# Carrier_Board_PIR.net
KiCad netlist of a schematic drawn in EAGLE
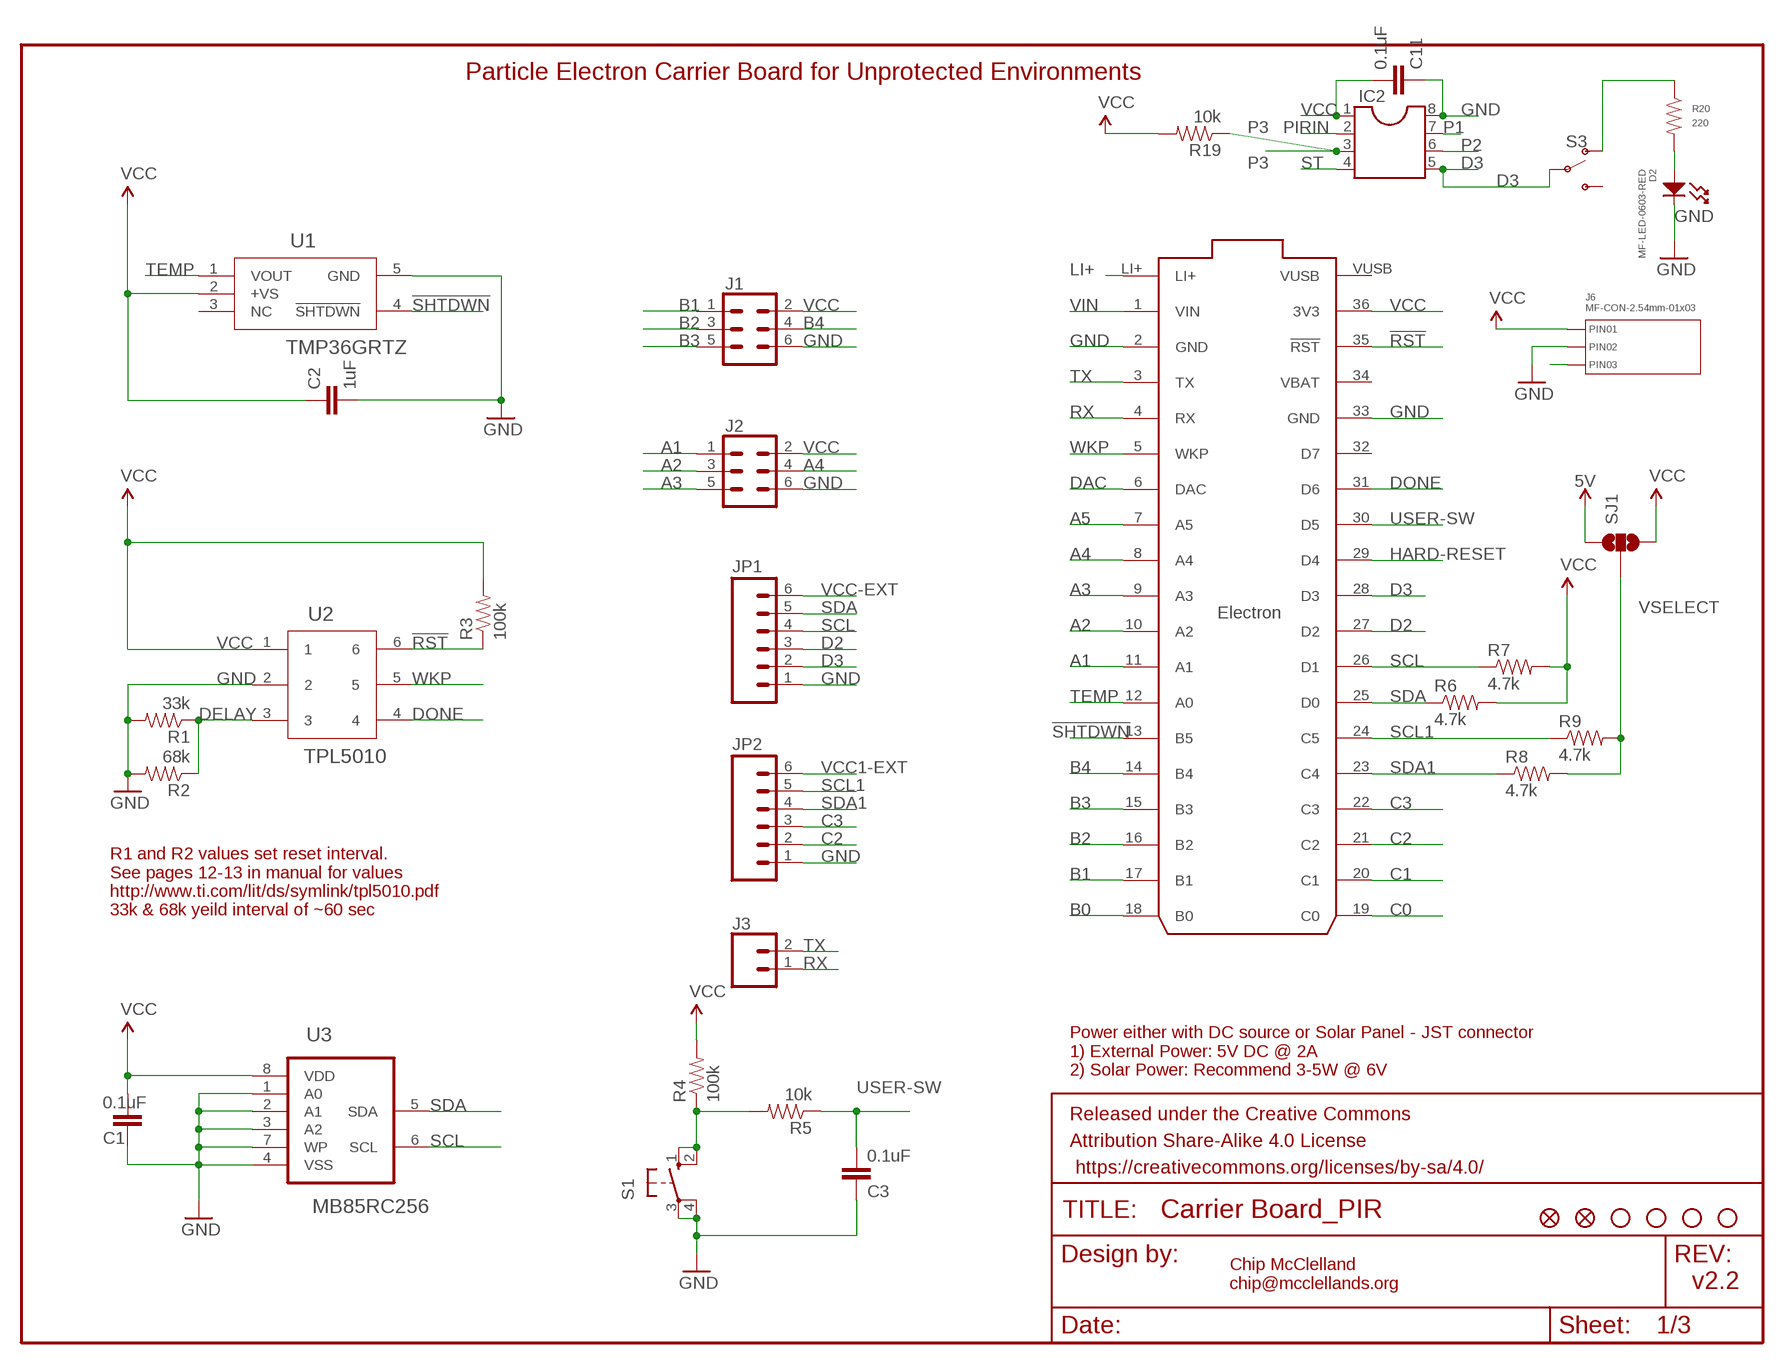
[diagram p0: schematic, sheet 1]
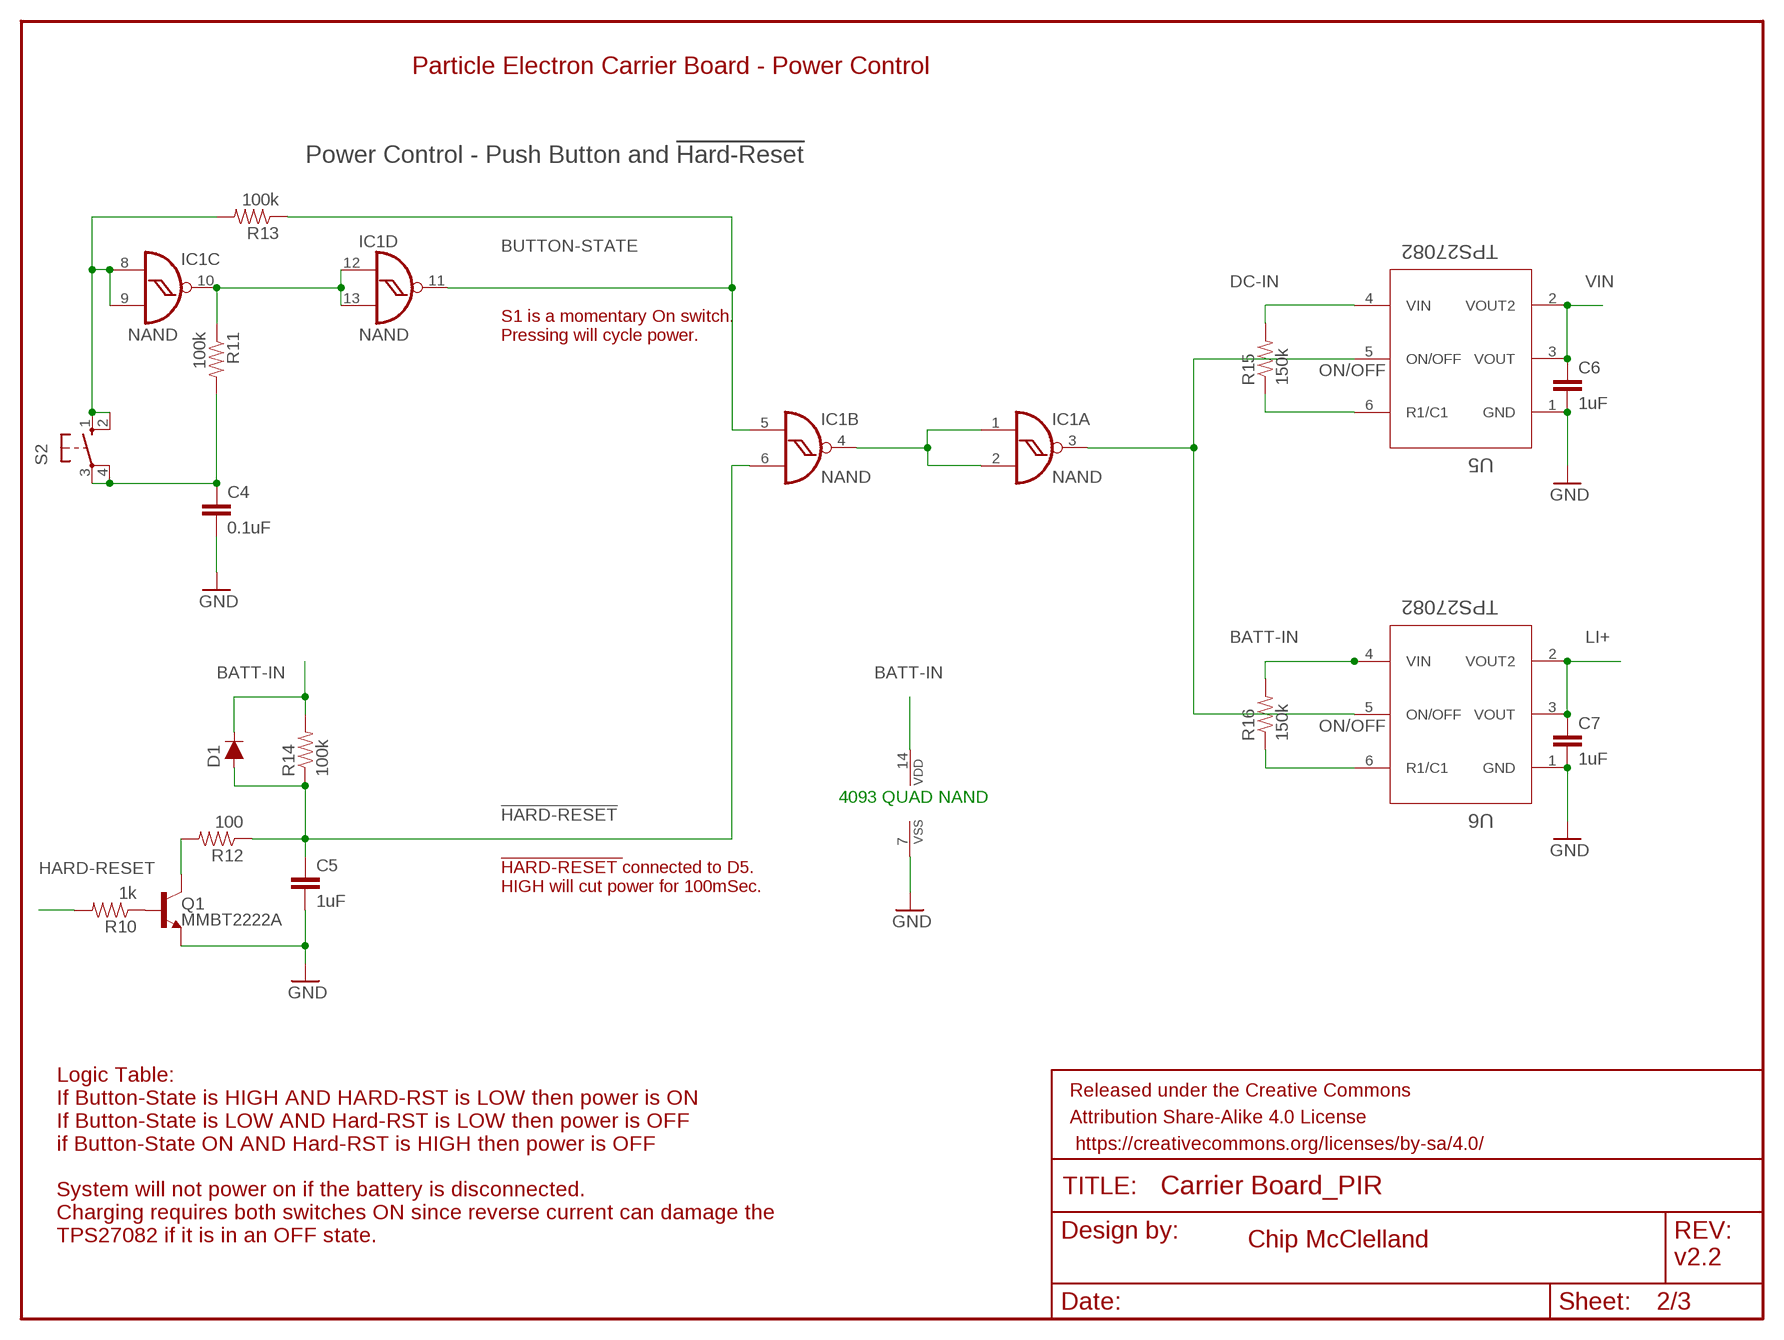
[diagram p1: schematic, sheet 2]
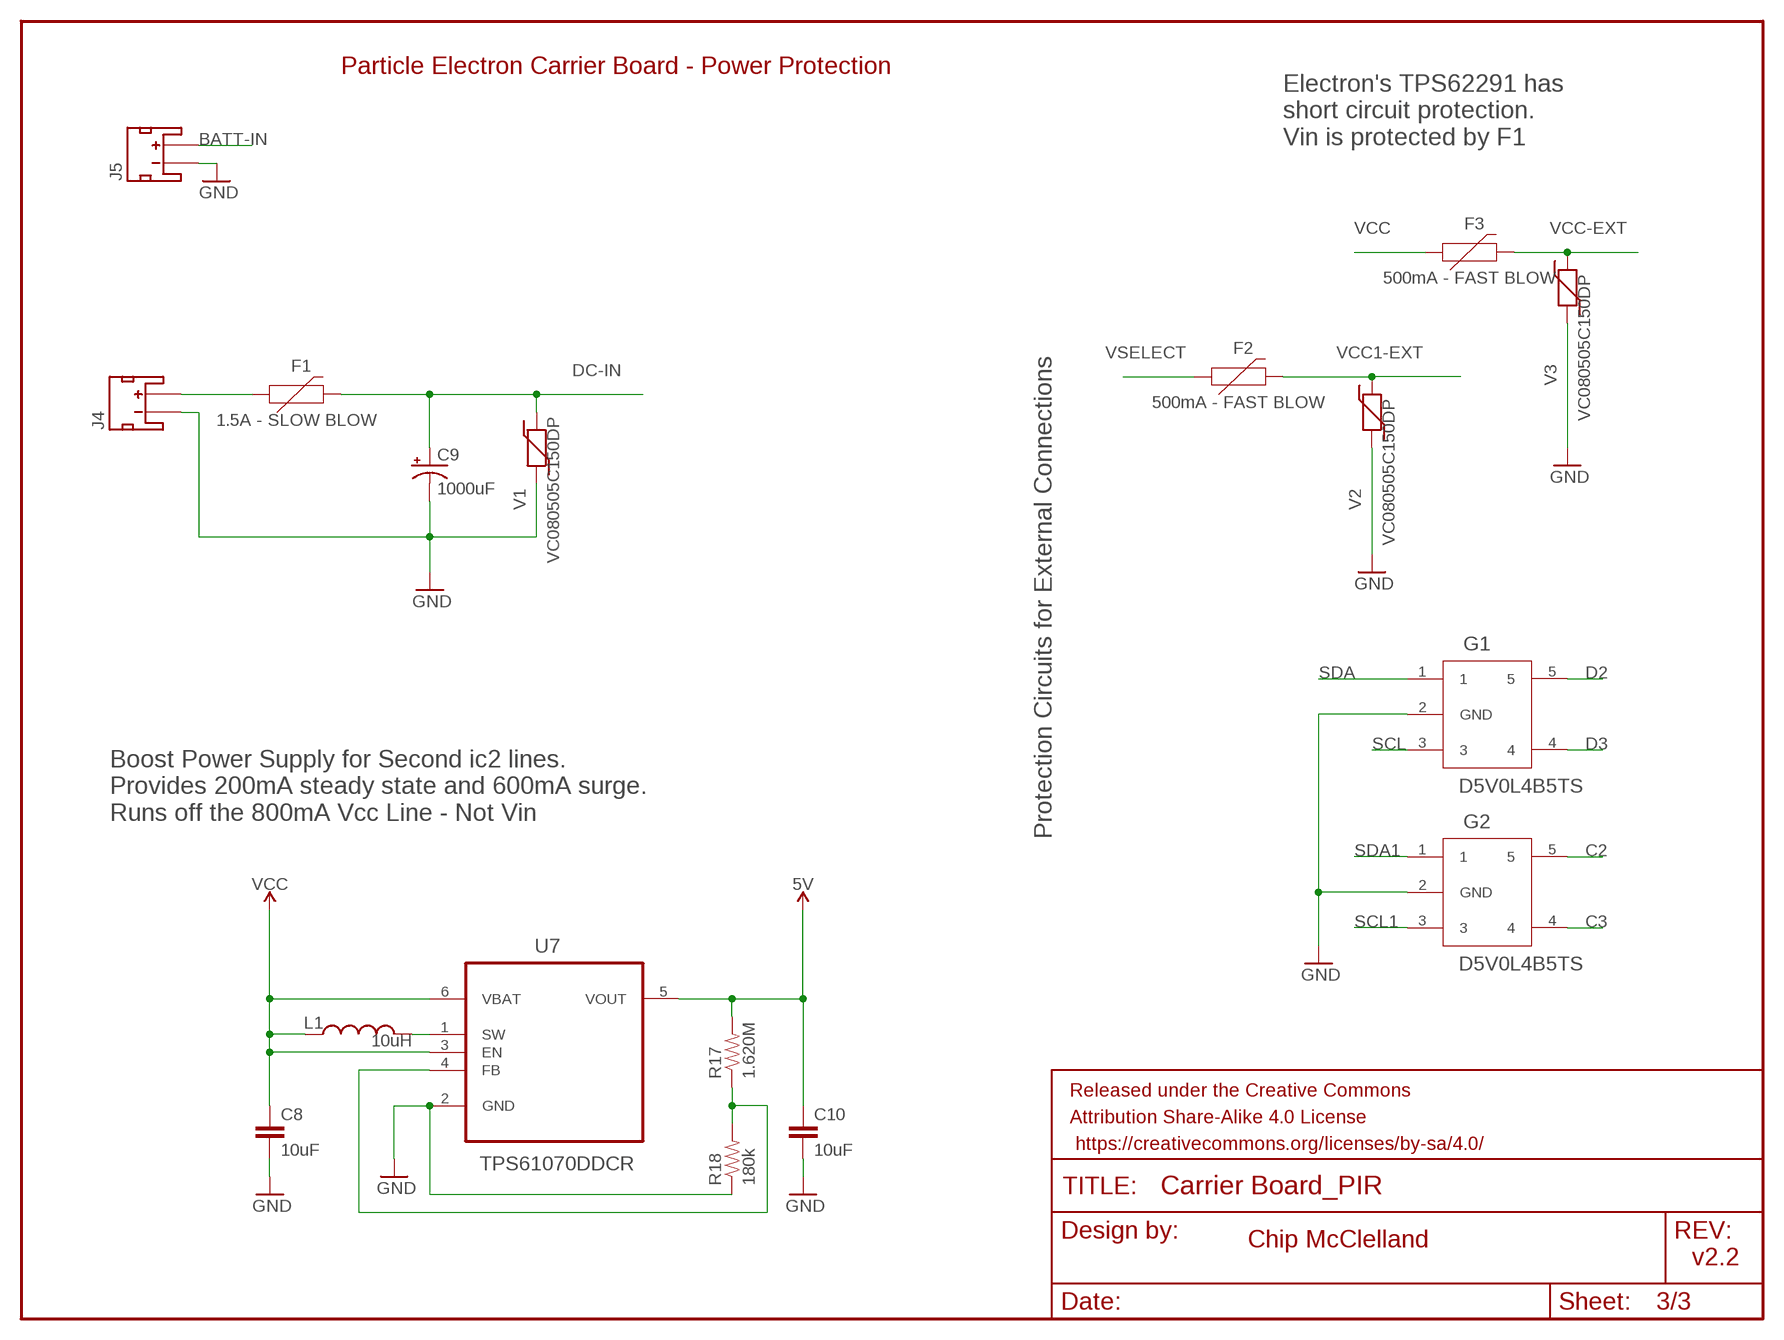
[diagram p2: schematic, sheet 3]

(export (version "E")
  (design (tool "Eeschema 10.0.6"))
  (components
    (comp (ref "C8")
      (value "10uF")
      (footprint "eagle-import:0805")
      (libsource (lib "eagle-import") (part "CAP0805"))
    )
    (comp (ref "C9")
      (value "1000uF")
      (footprint "eagle-import:PANASONIC_G")
      (libsource (lib "eagle-import") (part "CAP_POLG"))
    )
    (comp (ref "C10")
      (value "10uF")
      (footprint "eagle-import:0805")
      (libsource (lib "eagle-import") (part "CAP0805"))
    )
    (comp (ref "F1")
      (value "1.5A - SLOW BLOW")
      (footprint "eagle-import:1206")
      (libsource (lib "eagle-import") (part "PPTC_HALF-AMP"))
    )
    (comp (ref "F2")
      (value "500mA - FAST BLOW")
      (footprint "eagle-import:1206")
      (libsource (lib "eagle-import") (part "PPTC_HALF-AMP"))
    )
    (comp (ref "F3")
      (value "500mA - FAST BLOW")
      (footprint "eagle-import:1206")
      (libsource (lib "eagle-import") (part "PPTC_HALF-AMP"))
    )
    (comp (ref "FRAME3")
      (value "FRAME-LETTER")
      (footprint "eagle-import:CREATIVE_COMMONS")
      (libsource (lib "eagle-import") (part "FRAME-LETTER"))
    )
    (comp (ref "G1")
      (value "D5V0L4B5TS")
      (footprint "eagle-import:SOT-23-5")
      (libsource (lib "eagle-import") (part "D5V0L4B5TS"))
    )
    (comp (ref "G2")
      (value "D5V0L4B5TS")
      (footprint "eagle-import:SOT-23-5")
      (libsource (lib "eagle-import") (part "D5V0L4B5TS"))
    )
    (comp (ref "J4")
      (value "5V @ 2A")
      (footprint "eagle-import:JST-2-SMD")
      (libsource (lib "eagle-import") (part "JST_2MM_MALE"))
    )
    (comp (ref "J5")
      (value "JST_2MM_MALE")
      (footprint "eagle-import:JST-2-SMD")
      (libsource (lib "eagle-import") (part "JST_2MM_MALE"))
    )
    (comp (ref "L1")
      (value "10uH")
      (footprint "eagle-import:SDR0403")
      (libsource (lib "eagle-import") (part "INDUCTORSDR0403-560KL"))
    )
    (comp (ref "R17")
      (value "1.620M")
      (footprint "eagle-import:0805")
      (libsource (lib "eagle-import") (part "RESISTOR0805-RES"))
    )
    (comp (ref "R18")
      (value "180k")
      (footprint "eagle-import:0805")
      (libsource (lib "eagle-import") (part "RESISTOR0805-RES"))
    )
    (comp (ref "U7")
      (value "TPS61070DDCR")
      (footprint "eagle-import:SOT95P280X110-6N")
      (libsource (lib "eagle-import") (part "TPS61070DDCR"))
    )
    (comp (ref "V1")
      (value "VC080505C150DP")
      (footprint "eagle-import:0805")
      (libsource (lib "eagle-import") (part "VARISTOR"))
    )
    (comp (ref "V2")
      (value "VC080505C150DP")
      (footprint "eagle-import:0805")
      (libsource (lib "eagle-import") (part "VARISTOR"))
    )
    (comp (ref "V3")
      (value "VC080505C150DP")
      (footprint "eagle-import:0805")
      (libsource (lib "eagle-import") (part "VARISTOR"))
    )
    (comp (ref "C1")
      (value "0.1uF")
      (footprint "eagle-import:0805")
      (libsource (lib "eagle-import") (part "CAP0805"))
    )
    (comp (ref "C2")
      (value "1uF")
      (footprint "eagle-import:0805")
      (libsource (lib "eagle-import") (part "CAP0805"))
    )
    (comp (ref "C3")
      (value "0.1uF")
      (footprint "eagle-import:0805")
      (libsource (lib "eagle-import") (part "CAP0805"))
    )
    (comp (ref "C11")
      (value "0.1uF")
      (footprint "eagle-import:0805")
      (libsource (lib "eagle-import") (part "CAP0805"))
    )
    (comp (ref "D2")
      (value "MF-LED-0603-RED")
      (footprint "eagle-import:LED0603")
      (fields (field (name "HOUSEPART") "YES"))
      (libsource (lib "eagle-import") (part "LED_SINGLE-0603-RED"))
    )
    (comp (ref "FD1")
      (value "FIDUCIALUFIDUCIAL")
      (footprint "eagle-import:FIDUCIAL-MICRO")
      (libsource (lib "eagle-import") (part "FIDUCIALUFIDUCIAL"))
    )
    (comp (ref "FD2")
      (value "FIDUCIALUFIDUCIAL")
      (footprint "eagle-import:FIDUCIAL-MICRO")
      (libsource (lib "eagle-import") (part "FIDUCIALUFIDUCIAL"))
    )
    (comp (ref "FRAME1")
      (value "FRAME-LETTER")
      (footprint "eagle-import:CREATIVE_COMMONS")
      (libsource (lib "eagle-import") (part "FRAME-LETTER"))
    )
    (comp (ref "IC2")
      (value "DIL8S")
      (footprint "eagle-import:SOCKET-08")
      (libsource (lib "eagle-import") (part "DIL8S"))
    )
    (comp (ref "J1")
      (value "CONN_03X22X3_SILK_MALE_PTH")
      (footprint "eagle-import:2X3")
      (libsource (lib "eagle-import") (part "CONN_03X22X3_SILK_MALE_PTH"))
    )
    (comp (ref "J2")
      (value "CONN_03X22X3_SILK_MALE_PTH")
      (footprint "eagle-import:2X3")
      (libsource (lib "eagle-import") (part "CONN_03X22X3_SILK_MALE_PTH"))
    )
    (comp (ref "J3")
      (value "CONN_02")
      (footprint "eagle-import:1X02")
      (libsource (lib "eagle-import") (part "CONN_02"))
    )
    (comp (ref "J6")
      (value "MF-CON-2.54mm-01x03")
      (footprint "eagle-import:PTH_2.54MM_01X03")
      (fields (field (name "HOUSEPART") "YES"))
      (libsource (lib "eagle-import") (part "CON_01X03_PTH_2.54MM"))
    )
    (comp (ref "JP1")
      (value "M06LOCK")
      (footprint "eagle-import:1X06_LOCK")
      (libsource (lib "eagle-import") (part "M06LOCK"))
    )
    (comp (ref "JP2")
      (value "M06LOCK")
      (footprint "eagle-import:1X06_LOCK")
      (libsource (lib "eagle-import") (part "M06LOCK"))
    )
    (comp (ref "JP3")
      (value "STAND-OFF")
      (footprint "eagle-import:STAND-OFF")
      (libsource (lib "eagle-import") (part "STAND-OFF"))
    )
    (comp (ref "JP4")
      (value "STAND-OFF")
      (footprint "eagle-import:STAND-OFF")
      (libsource (lib "eagle-import") (part "STAND-OFF"))
    )
    (comp (ref "JP5")
      (value "STAND-OFF")
      (footprint "eagle-import:STAND-OFF")
      (libsource (lib "eagle-import") (part "STAND-OFF"))
    )
    (comp (ref "JP6")
      (value "STAND-OFF")
      (footprint "eagle-import:STAND-OFF")
      (libsource (lib "eagle-import") (part "STAND-OFF"))
    )
    (comp (ref "R1")
      (value "33k")
      (footprint "eagle-import:0805")
      (libsource (lib "eagle-import") (part "RESISTOR0805-RES"))
    )
    (comp (ref "R2")
      (value "68k")
      (footprint "eagle-import:0805")
      (libsource (lib "eagle-import") (part "RESISTOR0805-RES"))
    )
    (comp (ref "R3")
      (value "100k")
      (footprint "eagle-import:0805")
      (libsource (lib "eagle-import") (part "RESISTOR0805-RES"))
    )
    (comp (ref "R4")
      (value "100k")
      (footprint "eagle-import:0805")
      (libsource (lib "eagle-import") (part "RESISTOR0805-RES"))
    )
    (comp (ref "R5")
      (value "10k")
      (footprint "eagle-import:0805")
      (libsource (lib "eagle-import") (part "RESISTOR0805-RES"))
    )
    (comp (ref "R6")
      (value "4.7k")
      (footprint "eagle-import:0805")
      (libsource (lib "eagle-import") (part "RESISTOR0805-RES"))
    )
    (comp (ref "R7")
      (value "4.7k")
      (footprint "eagle-import:0805")
      (libsource (lib "eagle-import") (part "RESISTOR0805-RES"))
    )
    (comp (ref "R8")
      (value "4.7k")
      (footprint "eagle-import:0805")
      (libsource (lib "eagle-import") (part "RESISTOR0805-RES"))
    )
    (comp (ref "R9")
      (value "4.7k")
      (footprint "eagle-import:0805")
      (libsource (lib "eagle-import") (part "RESISTOR0805-RES"))
    )
    (comp (ref "R19")
      (value "10k")
      (footprint "eagle-import:0805")
      (libsource (lib "eagle-import") (part "RESISTOR0805-RES"))
    )
    (comp (ref "R20")
      (value "220")
      (footprint "eagle-import:R0603")
      (libsource (lib "eagle-import") (part "RESISTOR_0603"))
    )
    (comp (ref "S1")
      (value "10-XX")
      (footprint "eagle-import:B3F-10XX")
      (libsource (lib "eagle-import") (part "10-XX"))
    )
    (comp (ref "S3")
      (value "SWITCH-SPDT-SMD-RIGHT-ANGLE")
      (footprint "eagle-import:SWITCH_SPST_SMD_A")
      (libsource (lib "eagle-import") (part "SWITCH-SPDT-SMD-RIGHT-ANGLE"))
    )
    (comp (ref "SJ1")
      (value "SOLDERJUMPER_2WAYPASTE1&2")
      (footprint "eagle-import:SJ_3_PASTE1&2")
      (libsource (lib "eagle-import") (part "SOLDERJUMPER_2WAYPASTE1&2"))
    )
    (comp (ref "U1")
      (value "TMP36GRTZ")
      (footprint "eagle-import:RJ_5")
      (fields (field (name "MANUFACTURER_PART_NUMBER") "TMP36GRTZREEL7"))
      (libsource (lib "eagle-import") (part "TMP36GRTZ-REEL7"))
    )
    (comp (ref "U2")
      (value "TPL5010")
      (footprint "eagle-import:TSOT-23")
      (libsource (lib "eagle-import") (part "TPL5010"))
    )
    (comp (ref "U3")
      (value "MB85RC256")
      (footprint "eagle-import:SOIC127P600X175-8N")
      (fields (field (name "MPN") "MB85RC128PNF-G-JNE1"))
      (libsource (lib "eagle-import") (part "MB85RC128PNF-G-JNE1"))
    )
    (comp (ref "U4")
      (value "Particle Electron")
      (footprint "eagle-import:ELECTON-PWR-PINS")
      (libsource (lib "eagle-import") (part "ELECTRON-PWR-PINS"))
    )
    (comp (ref "C4")
      (value "0.1uF")
      (footprint "eagle-import:0805")
      (libsource (lib "eagle-import") (part "CAP0805"))
    )
    (comp (ref "C5")
      (value "1uF")
      (footprint "eagle-import:0805")
      (libsource (lib "eagle-import") (part "CAP0805"))
    )
    (comp (ref "C6")
      (value "1uF")
      (footprint "eagle-import:0805")
      (libsource (lib "eagle-import") (part "CAP0805"))
    )
    (comp (ref "C7")
      (value "1uF")
      (footprint "eagle-import:0805")
      (libsource (lib "eagle-import") (part "CAP0805"))
    )
    (comp (ref "D1")
      (value "DIODE-BAS16J")
      (footprint "eagle-import:SOD-323")
      (libsource (lib "eagle-import") (part "DIODE-BAS16J"))
    )
    (comp (ref "FRAME2")
      (value "FRAME-LETTER")
      (footprint "eagle-import:CREATIVE_COMMONS")
      (libsource (lib "eagle-import") (part "FRAME-LETTER"))
    )
    (comp (ref "IC1")
      (value "NAND")
      (footprint "eagle-import:MC14093B-TSSOP14")
      (libsource (lib "eagle-import") (part "4093DT"))
    )
    (comp (ref "Q1")
      (value "MMBT2222A")
      (footprint "eagle-import:SOT23-3")
      (libsource (lib "eagle-import") (part "TRANS_NPN-MMBT2222AL"))
    )
    (comp (ref "R10")
      (value "1k")
      (footprint "eagle-import:0805")
      (libsource (lib "eagle-import") (part "RESISTOR0805-RES"))
    )
    (comp (ref "R11")
      (value "100k")
      (footprint "eagle-import:0805")
      (libsource (lib "eagle-import") (part "RESISTOR0805-RES"))
    )
    (comp (ref "R12")
      (value "100")
      (footprint "eagle-import:0805")
      (libsource (lib "eagle-import") (part "RESISTOR0805-RES"))
    )
    (comp (ref "R13")
      (value "100k")
      (footprint "eagle-import:0805")
      (libsource (lib "eagle-import") (part "RESISTOR0805-RES"))
    )
    (comp (ref "R14")
      (value "100k")
      (footprint "eagle-import:0805")
      (libsource (lib "eagle-import") (part "RESISTOR0805-RES"))
    )
    (comp (ref "R15")
      (value "150k")
      (footprint "eagle-import:0805")
      (libsource (lib "eagle-import") (part "RESISTOR0805-RES"))
    )
    (comp (ref "R16")
      (value "150k")
      (footprint "eagle-import:0805")
      (libsource (lib "eagle-import") (part "RESISTOR0805-RES"))
    )
    (comp (ref "S2")
      (value "40-XX-ROUND")
      (footprint "eagle-import:B3F-40XX-ROUND")
      (libsource (lib "eagle-import") (part "40-XX-ROUND"))
    )
    (comp (ref "U5")
      (value "TPS27082")
      (footprint "eagle-import:TSOT-23")
      (libsource (lib "eagle-import") (part "TPS27082"))
    )
    (comp (ref "U6")
      (value "TPS27082")
      (footprint "eagle-import:TSOT-23")
      (libsource (lib "eagle-import") (part "TPS27082"))
    )
  )
  (nets
    (net (code "1") (name "5V") (class "Default")
      (node (ref "C10") (pin "1") (pinfunction "1_1") (pintype "passive"))
      (node (ref "R17") (pin "2") (pinfunction "2_2") (pintype "passive"))
      (node (ref "SJ1") (pin "1") (pinfunction "1_1") (pintype "passive"))
      (node (ref "U7") (pin "5") (pinfunction "VOUT_5") (pintype "output"))
    )
    (net (code "2") (name "A1") (class "Default")
      (node (ref "J2") (pin "1") (pinfunction "1_1") (pintype "bidirectional"))
      (node (ref "U4") (pin "11") (pinfunction "A1_11") (pintype "bidirectional"))
    )
    (net (code "3") (name "A2") (class "Default")
      (node (ref "J2") (pin "3") (pinfunction "3_3") (pintype "bidirectional"))
      (node (ref "U4") (pin "10") (pinfunction "A2_10") (pintype "bidirectional"))
    )
    (net (code "4") (name "A3") (class "Default")
      (node (ref "J2") (pin "5") (pinfunction "5_5") (pintype "bidirectional"))
      (node (ref "U4") (pin "9") (pinfunction "A3_9") (pintype "bidirectional"))
    )
    (net (code "5") (name "A4") (class "Default")
      (node (ref "J2") (pin "4") (pinfunction "4_4") (pintype "bidirectional"))
      (node (ref "U4") (pin "8") (pinfunction "A4_8") (pintype "bidirectional"))
    )
    (net (code "6") (name "A5") (class "Default")
      (node (ref "U4") (pin "7") (pinfunction "A5_7") (pintype "bidirectional"))
    )
    (net (code "7") (name "B0") (class "Default")
      (node (ref "U4") (pin "18") (pinfunction "B0_18") (pintype "bidirectional"))
    )
    (net (code "8") (name "B1") (class "Default")
      (node (ref "J1") (pin "1") (pinfunction "1_1") (pintype "bidirectional"))
      (node (ref "U4") (pin "17") (pinfunction "B1_17") (pintype "bidirectional"))
    )
    (net (code "9") (name "B2") (class "Default")
      (node (ref "J1") (pin "3") (pinfunction "3_3") (pintype "bidirectional"))
      (node (ref "U4") (pin "16") (pinfunction "B2_16") (pintype "bidirectional"))
    )
    (net (code "10") (name "B3") (class "Default")
      (node (ref "J1") (pin "5") (pinfunction "5_5") (pintype "bidirectional"))
      (node (ref "U4") (pin "15") (pinfunction "B3_15") (pintype "bidirectional"))
    )
    (net (code "11") (name "B4") (class "Default")
      (node (ref "J1") (pin "4") (pinfunction "4_4") (pintype "bidirectional"))
      (node (ref "U4") (pin "14") (pinfunction "B4_14") (pintype "bidirectional"))
    )
    (net (code "12") (name "BATT-IN") (class "Default")
      (node (ref "D1") (pin "C") (pinfunction "C_C") (pintype "passive"))
      (node (ref "IC1") (pin "14") (pinfunction "VDD_14") (pintype "power_in"))
      (node (ref "J5") (pin "2") (pinfunction "+_2") (pintype "bidirectional"))
      (node (ref "R14") (pin "2") (pinfunction "2_2") (pintype "passive"))
      (node (ref "R16") (pin "2") (pinfunction "2_2") (pintype "passive"))
      (node (ref "U6") (pin "4") (pinfunction "VIN_4") (pintype "input"))
    )
    (net (code "13") (name "BUTTON-STATE") (class "Default")
      (node (ref "IC1") (pin "11") (pinfunction "O_11") (pintype "output"))
      (node (ref "IC1") (pin "5") (pinfunction "I0_5") (pintype "input"))
      (node (ref "R13") (pin "1") (pinfunction "1_1") (pintype "passive"))
    )
    (net (code "14") (name "C0") (class "Default")
      (node (ref "U4") (pin "19") (pinfunction "C0_19") (pintype "bidirectional"))
    )
    (net (code "15") (name "C1") (class "Default")
      (node (ref "U4") (pin "20") (pinfunction "C1_20") (pintype "bidirectional"))
    )
    (net (code "16") (name "C2") (class "Default")
      (node (ref "G2") (pin "5") (pinfunction "5_5") (pintype "power_in"))
      (node (ref "JP2") (pin "2") (pinfunction "2_2") (pintype "passive"))
      (node (ref "U4") (pin "21") (pinfunction "C2_21") (pintype "bidirectional"))
    )
    (net (code "17") (name "C3") (class "Default")
      (node (ref "G2") (pin "4") (pinfunction "4_4") (pintype "input"))
      (node (ref "JP2") (pin "3") (pinfunction "3_3") (pintype "passive"))
      (node (ref "U4") (pin "22") (pinfunction "C3_22") (pintype "bidirectional"))
    )
    (net (code "18") (name "D2") (class "Default")
      (node (ref "G1") (pin "5") (pinfunction "5_5") (pintype "power_in"))
      (node (ref "JP1") (pin "3") (pinfunction "3_3") (pintype "passive"))
      (node (ref "U4") (pin "27") (pinfunction "D2_27") (pintype "bidirectional"))
    )
    (net (code "19") (name "D3") (class "Default")
      (node (ref "G1") (pin "4") (pinfunction "4_4") (pintype "input"))
      (node (ref "IC2") (pin "5") (pinfunction "5_5") (pintype "passive"))
      (node (ref "JP1") (pin "2") (pinfunction "2_2") (pintype "passive"))
      (node (ref "S3") (pin "2") (pinfunction "P_2") (pintype "passive"))
      (node (ref "U4") (pin "28") (pinfunction "D3_28") (pintype "bidirectional"))
    )
    (net (code "20") (name "DAC") (class "Default")
      (node (ref "U4") (pin "6") (pinfunction "DAC_6") (pintype "bidirectional"))
    )
    (net (code "21") (name "DC-IN") (class "Default")
      (node (ref "C9") (pin "+") (pinfunction "+_+") (pintype "passive"))
      (node (ref "F1") (pin "2") (pinfunction "2_2") (pintype "bidirectional"))
      (node (ref "R15") (pin "2") (pinfunction "2_2") (pintype "passive"))
      (node (ref "U5") (pin "4") (pinfunction "VIN_4") (pintype "input"))
      (node (ref "V1") (pin "2") (pinfunction "2_2") (pintype "passive"))
    )
    (net (code "22") (name "DELAY") (class "Default")
      (node (ref "R1") (pin "1") (pinfunction "1_1") (pintype "passive"))
      (node (ref "R2") (pin "1") (pinfunction "1_1") (pintype "passive"))
      (node (ref "U2") (pin "3") (pinfunction "3_3") (pintype "power_in"))
    )
    (net (code "23") (name "DONE") (class "Default")
      (node (ref "U2") (pin "4") (pinfunction "4_4") (pintype "input"))
      (node (ref "U4") (pin "31") (pinfunction "D6_31") (pintype "bidirectional"))
    )
    (net (code "24") (name "GND") (class "Default")
      (node (ref "C1") (pin "2") (pinfunction "2_2") (pintype "passive"))
      (node (ref "C10") (pin "2") (pinfunction "2_2") (pintype "passive"))
      (node (ref "C11") (pin "2") (pinfunction "2_2") (pintype "passive"))
      (node (ref "C2") (pin "2") (pinfunction "2_2") (pintype "passive"))
      (node (ref "C3") (pin "2") (pinfunction "2_2") (pintype "passive"))
      (node (ref "C4") (pin "2") (pinfunction "2_2") (pintype "passive"))
      (node (ref "C5") (pin "2") (pinfunction "2_2") (pintype "passive"))
      (node (ref "C6") (pin "2") (pinfunction "2_2") (pintype "passive"))
      (node (ref "C7") (pin "2") (pinfunction "2_2") (pintype "passive"))
      (node (ref "C8") (pin "2") (pinfunction "2_2") (pintype "passive"))
      (node (ref "C9") (pin "-") (pinfunction "-_-") (pintype "passive"))
      (node (ref "D2") (pin "CATHODE") (pinfunction "CATHODE_CATHODE") (pintype "power_in"))
      (node (ref "G1") (pin "2") (pinfunction "GND_2") (pintype "input"))
      (node (ref "G2") (pin "2") (pinfunction "GND_2") (pintype "input"))
      (node (ref "IC1") (pin "7") (pinfunction "VSS_7") (pintype "power_in"))
      (node (ref "IC2") (pin "8") (pinfunction "8_8") (pintype "passive"))
      (node (ref "J1") (pin "6") (pinfunction "6_6") (pintype "bidirectional"))
      (node (ref "J2") (pin "6") (pinfunction "6_6") (pintype "bidirectional"))
      (node (ref "J4") (pin "1") (pinfunction "-_1") (pintype "bidirectional"))
      (node (ref "J5") (pin "1") (pinfunction "-_1") (pintype "bidirectional"))
      (node (ref "J6") (pin "P$2") (pinfunction "PIN2_P$2") (pintype "bidirectional"))
      (node (ref "JP1") (pin "1") (pinfunction "1_1") (pintype "passive"))
      (node (ref "JP2") (pin "1") (pinfunction "1_1") (pintype "passive"))
      (node (ref "Q1") (pin "2") (pinfunction "E_2") (pintype "passive"))
      (node (ref "R1") (pin "2") (pinfunction "2_2") (pintype "passive"))
      (node (ref "R18") (pin "1") (pinfunction "1_1") (pintype "passive"))
      (node (ref "R2") (pin "2") (pinfunction "2_2") (pintype "passive"))
      (node (ref "S1") (pin "3") (pinfunction "P_3") (pintype "passive"))
      (node (ref "S1") (pin "4") (pinfunction "P1_4") (pintype "passive"))
      (node (ref "U1") (pin "5") (pinfunction "GND_5") (pintype "passive"))
      (node (ref "U2") (pin "2") (pinfunction "2_2") (pintype "input"))
      (node (ref "U3") (pin "1") (pinfunction "A0_1") (pintype "input"))
      (node (ref "U3") (pin "2") (pinfunction "A1_2") (pintype "input"))
      (node (ref "U3") (pin "3") (pinfunction "A2_3") (pintype "input"))
      (node (ref "U3") (pin "4") (pinfunction "VSS_4") (pintype "passive"))
      (node (ref "U3") (pin "7") (pinfunction "WP_7") (pintype "input"))
      (node (ref "U4") (pin "2") (pinfunction "GND_2") (pintype "power_in"))
      (node (ref "U4") (pin "33") (pinfunction "GND_33") (pintype "power_in"))
      (node (ref "U5") (pin "1") (pinfunction "GND_1") (pintype "power_in"))
      (node (ref "U6") (pin "1") (pinfunction "GND_1") (pintype "power_in"))
      (node (ref "U7") (pin "2") (pinfunction "GND_2") (pintype "passive"))
      (node (ref "V1") (pin "1") (pinfunction "1_1") (pintype "passive"))
      (node (ref "V2") (pin "1") (pinfunction "1_1") (pintype "passive"))
      (node (ref "V3") (pin "1") (pinfunction "1_1") (pintype "passive"))
    )
    (net (code "25") (name "HARD-RESET") (class "Default")
      (node (ref "R10") (pin "2") (pinfunction "2_2") (pintype "passive"))
      (node (ref "U4") (pin "29") (pinfunction "D4_29") (pintype "bidirectional"))
    )
    (net (code "26") (name "LI+") (class "Default")
      (node (ref "C7") (pin "1") (pinfunction "1_1") (pintype "passive"))
      (node (ref "U4") (pin "LI+") (pinfunction "LI+_LI+") (pintype "bidirectional"))
      (node (ref "U6") (pin "2") (pinfunction "VOUT2_2") (pintype "power_in"))
      (node (ref "U6") (pin "3") (pinfunction "VOUT_3") (pintype "input"))
    )
    (net (code "27") (name "Net-(D2-PadANODE)") (class "Default")
      (node (ref "D2") (pin "ANODE") (pinfunction "ANODE_ANODE") (pintype "power_in"))
      (node (ref "R20") (pin "P$2") (pinfunction "P$2_P$2") (pintype "passive"))
    )
    (net (code "28") (name "Net-(IC1A-I0)") (class "Default")
      (node (ref "IC1") (pin "1") (pinfunction "I0_1") (pintype "input"))
      (node (ref "IC1") (pin "2") (pinfunction "I1_2") (pintype "input"))
      (node (ref "IC1") (pin "4") (pinfunction "O_4") (pintype "output"))
    )
    (net (code "29") (name "Net-(IC1C-I0)") (class "Default")
      (node (ref "IC1") (pin "8") (pinfunction "I0_8") (pintype "input"))
      (node (ref "IC1") (pin "9") (pinfunction "I1_9") (pintype "input"))
      (node (ref "R13") (pin "2") (pinfunction "2_2") (pintype "passive"))
      (node (ref "S2") (pin "1") (pinfunction "S_1") (pintype "passive"))
      (node (ref "S2") (pin "2") (pinfunction "S1_2") (pintype "passive"))
    )
    (net (code "30") (name "Net-(IC1C-O)") (class "Default")
      (node (ref "IC1") (pin "10") (pinfunction "O_10") (pintype "output"))
      (node (ref "IC1") (pin "12") (pinfunction "I0_12") (pintype "input"))
      (node (ref "IC1") (pin "13") (pinfunction "I1_13") (pintype "input"))
      (node (ref "R11") (pin "1") (pinfunction "1_1") (pintype "passive"))
    )
    (net (code "31") (name "Net-(J4-+)") (class "Default")
      (node (ref "F1") (pin "1") (pinfunction "1_1") (pintype "bidirectional"))
      (node (ref "J4") (pin "2") (pinfunction "+_2") (pintype "bidirectional"))
    )
    (net (code "32") (name "Net-(L1-2)") (class "Default")
      (node (ref "L1") (pin "P$2") (pinfunction "2_P$2") (pintype "passive"))
      (node (ref "U7") (pin "1") (pinfunction "SW_1") (pintype "input"))
    )
    (net (code "33") (name "Net-(Q1-B)") (class "Default")
      (node (ref "Q1") (pin "1") (pinfunction "B_1") (pintype "passive"))
      (node (ref "R10") (pin "1") (pinfunction "1_1") (pintype "passive"))
    )
    (net (code "34") (name "Net-(Q1-C)") (class "Default")
      (node (ref "Q1") (pin "3") (pinfunction "C_3") (pintype "passive"))
      (node (ref "R12") (pin "2") (pinfunction "2_2") (pintype "passive"))
    )
    (net (code "35") (name "Net-(S1-S)") (class "Default")
      (node (ref "R4") (pin "1") (pinfunction "1_1") (pintype "passive"))
      (node (ref "R5") (pin "2") (pinfunction "2_2") (pintype "passive"))
      (node (ref "S1") (pin "1") (pinfunction "S_1") (pintype "passive"))
      (node (ref "S1") (pin "2") (pinfunction "S1_2") (pintype "passive"))
    )
    (net (code "36") (name "Net-(S2-P)") (class "Default")
      (node (ref "C4") (pin "1") (pinfunction "1_1") (pintype "passive"))
      (node (ref "R11") (pin "2") (pinfunction "2_2") (pintype "passive"))
      (node (ref "S2") (pin "3") (pinfunction "P_3") (pintype "passive"))
      (node (ref "S2") (pin "4") (pinfunction "P1_4") (pintype "passive"))
    )
    (net (code "37") (name "Net-(S3-O)") (class "Default")
      (node (ref "R20") (pin "P$1") (pinfunction "P$1_P$1") (pintype "passive"))
      (node (ref "S3") (pin "1") (pinfunction "O_1") (pintype "passive"))
    )
    (net (code "38") (name "Net-(U5-R1{slash}C1)") (class "Default")
      (node (ref "R15") (pin "1") (pinfunction "1_1") (pintype "passive"))
      (node (ref "U5") (pin "6") (pinfunction "R1/C1_6") (pintype "power_in"))
    )
    (net (code "39") (name "Net-(U6-R1{slash}C1)") (class "Default")
      (node (ref "R16") (pin "1") (pinfunction "1_1") (pintype "passive"))
      (node (ref "U6") (pin "6") (pinfunction "R1/C1_6") (pintype "power_in"))
    )
    (net (code "40") (name "Net-(U7-FB)") (class "Default")
      (node (ref "R17") (pin "1") (pinfunction "1_1") (pintype "passive"))
      (node (ref "R18") (pin "2") (pinfunction "2_2") (pintype "passive"))
      (node (ref "U7") (pin "4") (pinfunction "FB_4") (pintype "input"))
    )
    (net (code "41") (name "ON{slash}OFF") (class "Default")
      (node (ref "IC1") (pin "3") (pinfunction "O_3") (pintype "output"))
      (node (ref "U5") (pin "5") (pinfunction "ON/OFF_5") (pintype "bidirectional"))
      (node (ref "U6") (pin "5") (pinfunction "ON/OFF_5") (pintype "bidirectional"))
    )
    (net (code "42") (name "P1") (class "Default")
      (node (ref "IC2") (pin "7") (pinfunction "7_7") (pintype "passive"))
    )
    (net (code "43") (name "P2") (class "Default")
      (node (ref "IC2") (pin "6") (pinfunction "6_6") (pintype "passive"))
    )
    (net (code "44") (name "P3") (class "Default")
      (node (ref "IC2") (pin "3") (pinfunction "3_3") (pintype "passive"))
      (node (ref "R19") (pin "1") (pinfunction "1_1") (pintype "passive"))
    )
    (net (code "45") (name "PIRIN") (class "Default")
      (node (ref "IC2") (pin "2") (pinfunction "2_2") (pintype "passive"))
      (node (ref "J6") (pin "P$3") (pinfunction "PIN3_P$3") (pintype "bidirectional"))
    )
    (net (code "46") (name "RX") (class "Default")
      (node (ref "J3") (pin "1") (pinfunction "1_1") (pintype "passive"))
      (node (ref "U4") (pin "4") (pinfunction "RX_4") (pintype "bidirectional"))
    )
    (net (code "47") (name "SCL") (class "Default")
      (node (ref "G1") (pin "3") (pinfunction "3_3") (pintype "power_in"))
      (node (ref "JP1") (pin "4") (pinfunction "4_4") (pintype "passive"))
      (node (ref "R7") (pin "1") (pinfunction "1_1") (pintype "passive"))
      (node (ref "U3") (pin "6") (pinfunction "SCL_6") (pintype "input"))
      (node (ref "U4") (pin "26") (pinfunction "D1_26") (pintype "bidirectional"))
    )
    (net (code "48") (name "SCL1") (class "Default")
      (node (ref "G2") (pin "3") (pinfunction "3_3") (pintype "power_in"))
      (node (ref "JP2") (pin "5") (pinfunction "5_5") (pintype "passive"))
      (node (ref "R9") (pin "1") (pinfunction "1_1") (pintype "passive"))
      (node (ref "U4") (pin "24") (pinfunction "C5_24") (pintype "bidirectional"))
    )
    (net (code "49") (name "SDA") (class "Default")
      (node (ref "G1") (pin "1") (pinfunction "1_1") (pintype "power_in"))
      (node (ref "JP1") (pin "5") (pinfunction "5_5") (pintype "passive"))
      (node (ref "R6") (pin "1") (pinfunction "1_1") (pintype "passive"))
      (node (ref "U3") (pin "5") (pinfunction "SDA_5") (pintype "bidirectional"))
      (node (ref "U4") (pin "25") (pinfunction "D0_25") (pintype "bidirectional"))
    )
    (net (code "50") (name "SDA1") (class "Default")
      (node (ref "G2") (pin "1") (pinfunction "1_1") (pintype "power_in"))
      (node (ref "JP2") (pin "4") (pinfunction "4_4") (pintype "passive"))
      (node (ref "R8") (pin "1") (pinfunction "1_1") (pintype "passive"))
      (node (ref "U4") (pin "23") (pinfunction "C4_23") (pintype "bidirectional"))
    )
    (net (code "51") (name "ST") (class "Default")
      (node (ref "IC2") (pin "4") (pinfunction "4_4") (pintype "passive"))
    )
    (net (code "52") (name "TEMP") (class "Default")
      (node (ref "U1") (pin "1") (pinfunction "VOUT_1") (pintype "passive"))
      (node (ref "U4") (pin "12") (pinfunction "A0_12") (pintype "bidirectional"))
    )
    (net (code "53") (name "TX") (class "Default")
      (node (ref "J3") (pin "2") (pinfunction "2_2") (pintype "passive"))
      (node (ref "U4") (pin "3") (pinfunction "TX_3") (pintype "bidirectional"))
    )
    (net (code "54") (name "USER-SW") (class "Default")
      (node (ref "C3") (pin "1") (pinfunction "1_1") (pintype "passive"))
      (node (ref "R5") (pin "1") (pinfunction "1_1") (pintype "passive"))
      (node (ref "U4") (pin "30") (pinfunction "D5_30") (pintype "bidirectional"))
    )
    (net (code "55") (name "VBAT") (class "Default")
      (node (ref "U4") (pin "34") (pinfunction "VBAT_34") (pintype "power_in"))
    )
    (net (code "56") (name "VCC") (class "Default")
      (node (ref "C1") (pin "1") (pinfunction "1_1") (pintype "passive"))
      (node (ref "C11") (pin "1") (pinfunction "1_1") (pintype "passive"))
      (node (ref "C2") (pin "1") (pinfunction "1_1") (pintype "passive"))
      (node (ref "C8") (pin "1") (pinfunction "1_1") (pintype "passive"))
      (node (ref "F3") (pin "1") (pinfunction "1_1") (pintype "bidirectional"))
      (node (ref "IC2") (pin "1") (pinfunction "1_1") (pintype "passive"))
      (node (ref "J1") (pin "2") (pinfunction "2_2") (pintype "bidirectional"))
      (node (ref "J2") (pin "2") (pinfunction "2_2") (pintype "bidirectional"))
      (node (ref "J6") (pin "P$1") (pinfunction "PIN1_P$1") (pintype "bidirectional"))
      (node (ref "L1") (pin "P$1") (pinfunction "1_P$1") (pintype "passive"))
      (node (ref "R19") (pin "2") (pinfunction "2_2") (pintype "passive"))
      (node (ref "R3") (pin "2") (pinfunction "2_2") (pintype "passive"))
      (node (ref "R4") (pin "2") (pinfunction "2_2") (pintype "passive"))
      (node (ref "R6") (pin "2") (pinfunction "2_2") (pintype "passive"))
      (node (ref "R7") (pin "2") (pinfunction "2_2") (pintype "passive"))
      (node (ref "SJ1") (pin "3") (pinfunction "3_3") (pintype "passive"))
      (node (ref "U1") (pin "2") (pinfunction "+VS_2") (pintype "power_in"))
      (node (ref "U2") (pin "1") (pinfunction "1_1") (pintype "power_in"))
      (node (ref "U3") (pin "8") (pinfunction "VDD_8") (pintype "power_in"))
      (node (ref "U4") (pin "36") (pinfunction "3V3_36") (pintype "power_in"))
      (node (ref "U7") (pin "3") (pinfunction "EN_3") (pintype "input"))
      (node (ref "U7") (pin "6") (pinfunction "VBAT_6") (pintype "power_in"))
    )
    (net (code "57") (name "VCC-EXT") (class "Default")
      (node (ref "F3") (pin "2") (pinfunction "2_2") (pintype "bidirectional"))
      (node (ref "JP1") (pin "6") (pinfunction "6_6") (pintype "passive"))
      (node (ref "V3") (pin "2") (pinfunction "2_2") (pintype "passive"))
    )
    (net (code "58") (name "VCC1-EXT") (class "Default")
      (node (ref "F2") (pin "2") (pinfunction "2_2") (pintype "bidirectional"))
      (node (ref "JP2") (pin "6") (pinfunction "6_6") (pintype "passive"))
      (node (ref "V2") (pin "2") (pinfunction "2_2") (pintype "passive"))
    )
    (net (code "59") (name "VIN") (class "Default")
      (node (ref "C6") (pin "1") (pinfunction "1_1") (pintype "passive"))
      (node (ref "U4") (pin "1") (pinfunction "VIN_1") (pintype "power_in"))
      (node (ref "U5") (pin "2") (pinfunction "VOUT2_2") (pintype "power_in"))
      (node (ref "U5") (pin "3") (pinfunction "VOUT_3") (pintype "input"))
    )
    (net (code "60") (name "VSELECT") (class "Default")
      (node (ref "F2") (pin "1") (pinfunction "1_1") (pintype "bidirectional"))
      (node (ref "R8") (pin "2") (pinfunction "2_2") (pintype "passive"))
      (node (ref "R9") (pin "2") (pinfunction "2_2") (pintype "passive"))
      (node (ref "SJ1") (pin "2") (pinfunction "2_2") (pintype "passive"))
    )
    (net (code "61") (name "WKP") (class "Default")
      (node (ref "U2") (pin "5") (pinfunction "5_5") (pintype "bidirectional"))
      (node (ref "U4") (pin "5") (pinfunction "WKP_5") (pintype "bidirectional"))
    )
    (net (code "62") (name "unconnected-(J4-PAD1-PadNC1)") (class "Default")
      (node (ref "J4") (pin "NC1") (pinfunction "PAD1_NC1") (pintype "bidirectional"))
    )
    (net (code "63") (name "unconnected-(J4-PAD2-PadNC2)") (class "Default")
      (node (ref "J4") (pin "NC2") (pinfunction "PAD2_NC2") (pintype "bidirectional"))
    )
    (net (code "64") (name "unconnected-(J5-PAD1-PadNC1)") (class "Default")
      (node (ref "J5") (pin "NC1") (pinfunction "PAD1_NC1") (pintype "bidirectional"))
    )
    (net (code "65") (name "unconnected-(J5-PAD2-PadNC2)") (class "Default")
      (node (ref "J5") (pin "NC2") (pinfunction "PAD2_NC2") (pintype "bidirectional"))
    )
    (net (code "66") (name "unconnected-(S3-S-Pad3)") (class "Default")
      (node (ref "S3") (pin "3") (pinfunction "S_3") (pintype "passive"))
    )
    (net (code "67") (name "unconnected-(U1-NC-Pad3)") (class "Default")
      (node (ref "U1") (pin "3") (pinfunction "NC_3") (pintype "passive"))
    )
    (net (code "68") (name "unconnected-(U4-D7-Pad32)") (class "Default")
      (node (ref "U4") (pin "32") (pinfunction "D7_32") (pintype "bidirectional"))
    )
    (net (code "69") (name "unconnected-(U4-PadVUSB)") (class "Default")
      (node (ref "U4") (pin "VUSB") (pinfunction "VUSB_VUSB") (pintype "bidirectional"))
    )
    (net (code "70") (name "~{HARD-RESET}") (class "Default")
      (node (ref "C5") (pin "1") (pinfunction "1_1") (pintype "passive"))
      (node (ref "D1") (pin "A") (pinfunction "A_A") (pintype "passive"))
      (node (ref "IC1") (pin "6") (pinfunction "I1_6") (pintype "input"))
      (node (ref "R12") (pin "1") (pinfunction "1_1") (pintype "passive"))
      (node (ref "R14") (pin "1") (pinfunction "1_1") (pintype "passive"))
    )
    (net (code "71") (name "~{RST}") (class "Default")
      (node (ref "R3") (pin "1") (pinfunction "1_1") (pintype "passive"))
      (node (ref "U2") (pin "6") (pinfunction "6_6") (pintype "power_in"))
      (node (ref "U4") (pin "35") (pinfunction "~{RST}_35") (pintype "bidirectional"))
    )
    (net (code "72") (name "~{SHTDWN}") (class "Default")
      (node (ref "U1") (pin "4") (pinfunction "~{SHTDWN}_4") (pintype "passive"))
      (node (ref "U4") (pin "13") (pinfunction "B5_13") (pintype "bidirectional"))
    )
  )
)
